# PoE.net
KiCad netlist of a schematic drawn in Altium Designer
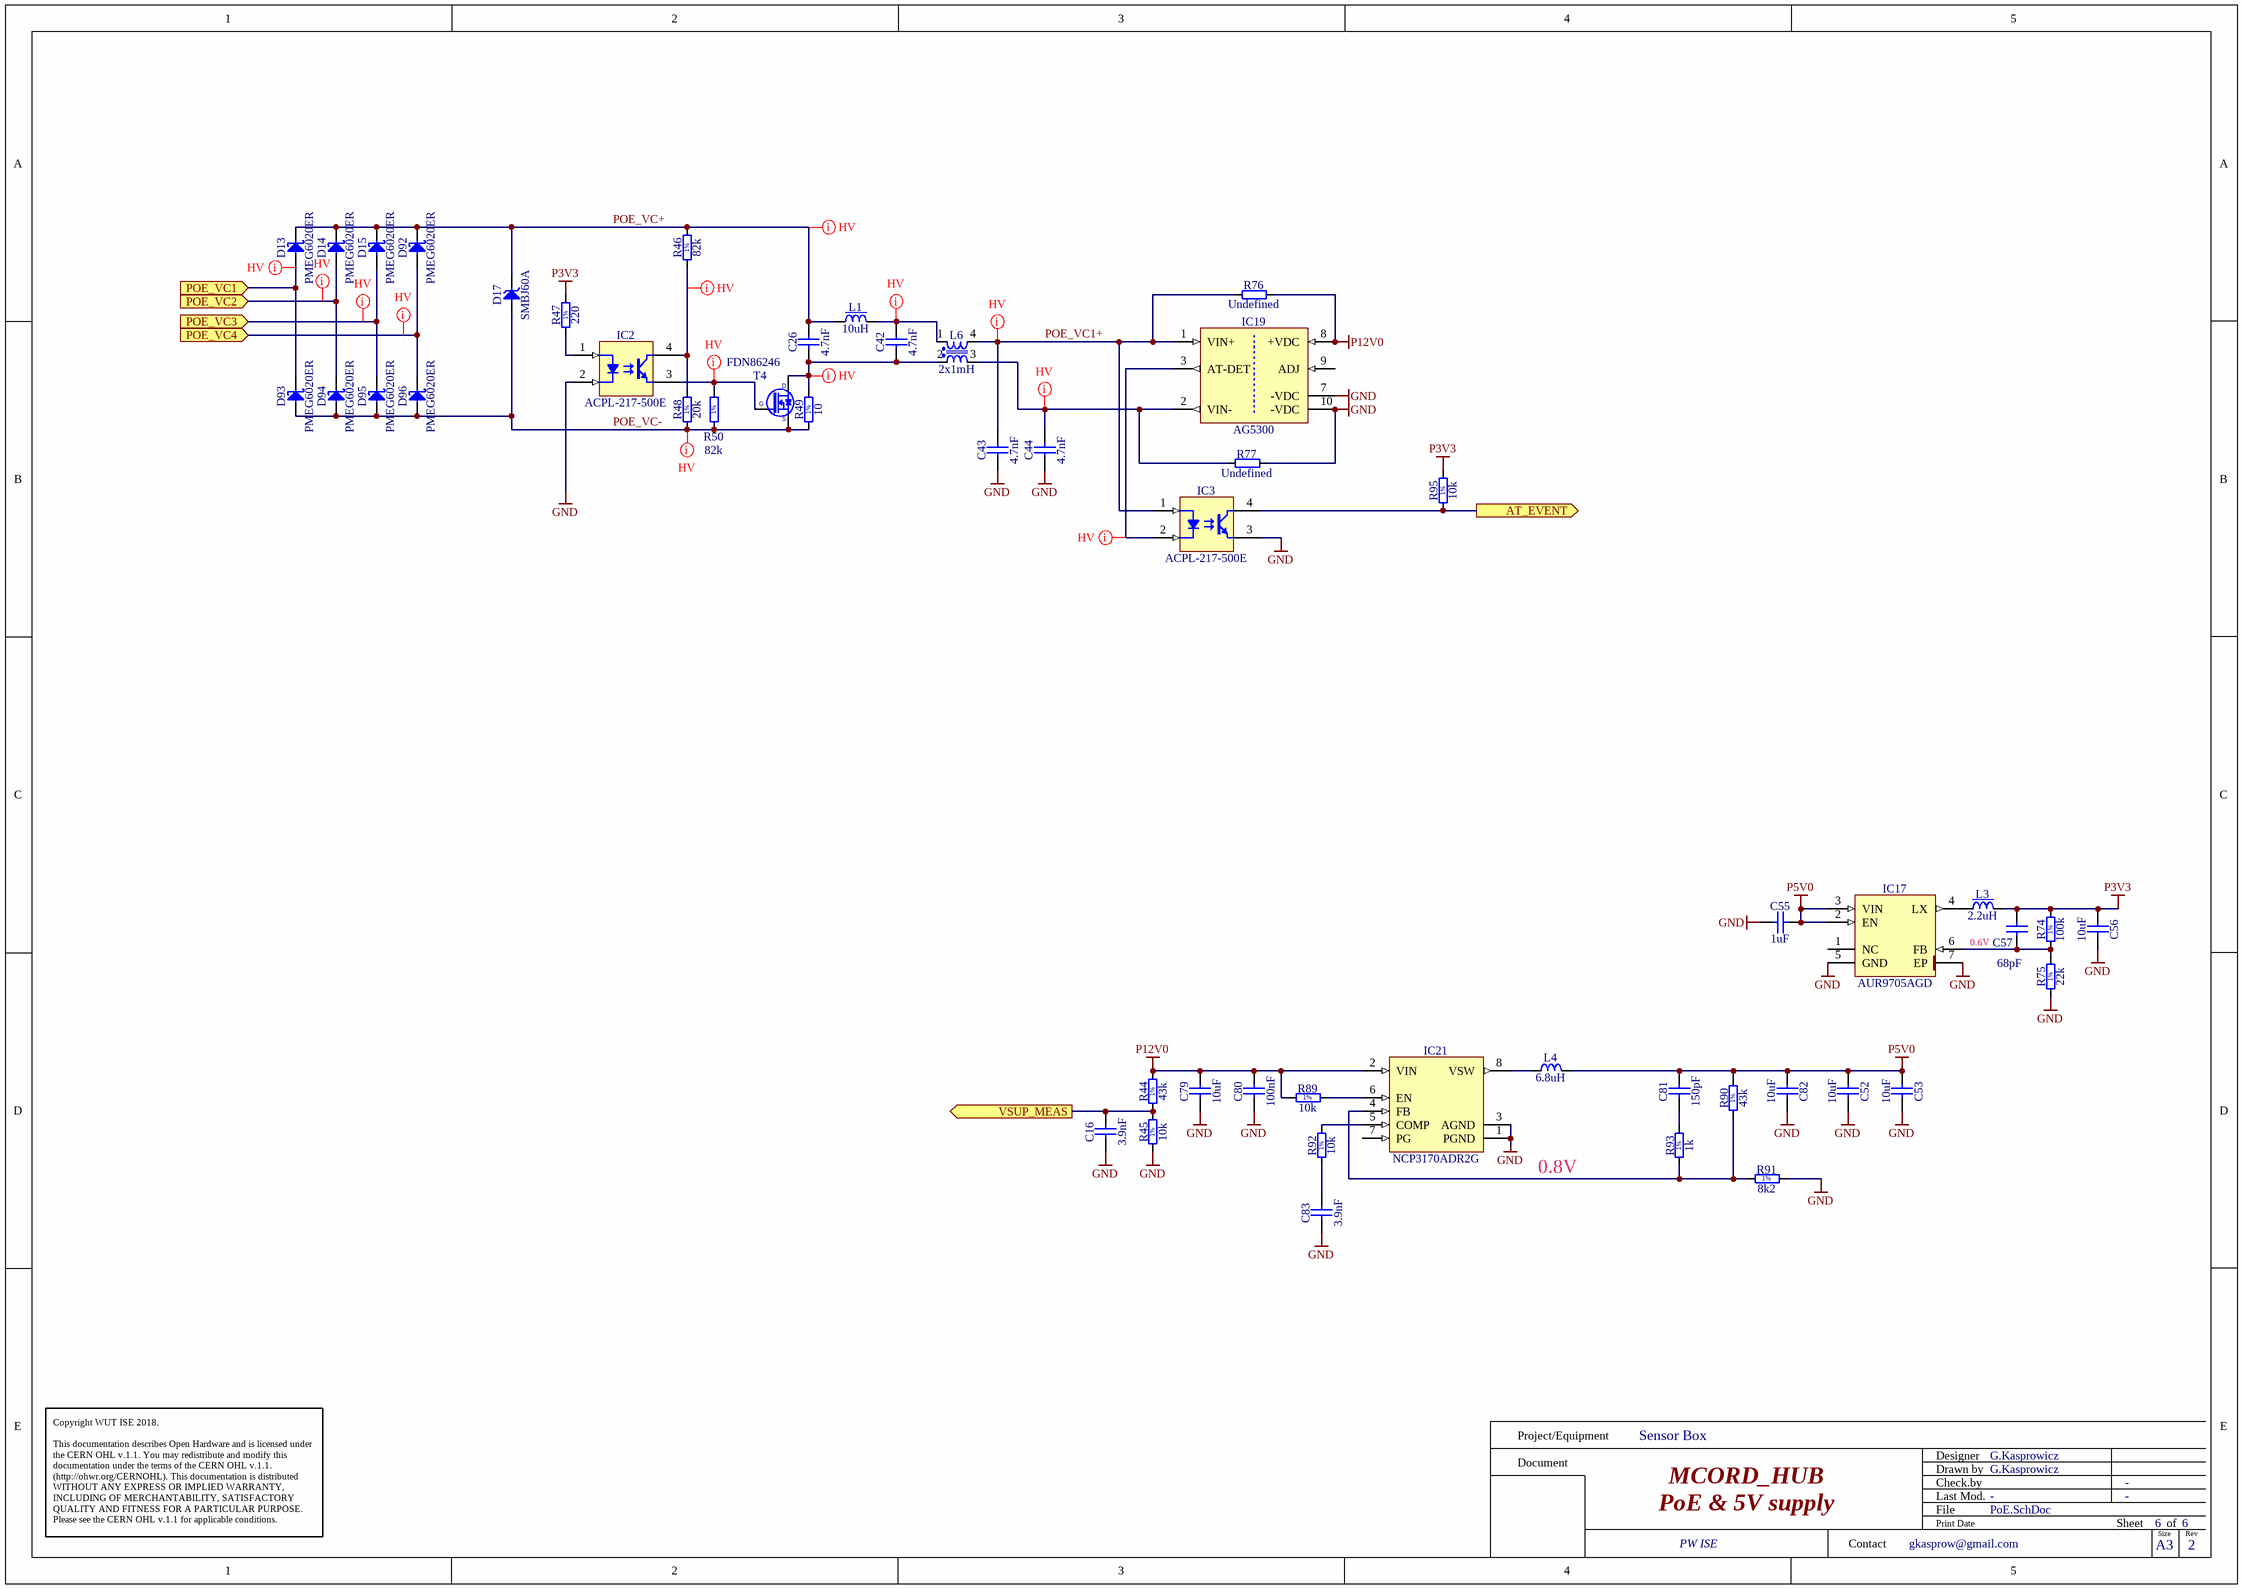
[diagram p0: PoE.SchDoc]

(export (version "E")
  (design (tool "Eeschema 10.0.6"))
  (components
    (comp (ref "C16")
      (value "3.9nF")
      (footprint "CAPC1608X87N")
      (description "Non-polarised capacitor")
      (fields
        (field (name "PART NUMBER") "CC0603_3.9NF_50V_5%_X7R")
        (field (name "VOLTAGE") "50V")
        (field (name "AUTHOR") "CERN DEM JLC")
      )
      (libsource (lib "Capacitors") (part "Capacitor - non polarized"))
    )
    (comp (ref "C26")
      (value "4.7nF")
      (footprint "CAPC3216X140N")
      (description "Non-polarised capacitor")
      (fields
        (field (name "PART NUMBER") "CC1206_4.7NF_500V_10%_X7R")
        (field (name "VOLTAGE") "500V")
        (field (name "AUTHOR") "GK")
      )
      (libsource (lib "LIBRARY_SCH") (part "CAP_SMD_1206_4.7n_500V"))
    )
    (comp (ref "C42")
      (value "4.7nF")
      (footprint "CAPC3216X140N")
      (description "Non-polarised capacitor")
      (fields
        (field (name "PART NUMBER") "CC1206_4.7NF_500V_10%_X7R")
        (field (name "VOLTAGE") "500V")
        (field (name "AUTHOR") "GK")
      )
      (libsource (lib "LIBRARY_SCH") (part "CAP_SMD_1206_4.7n_500V"))
    )
    (comp (ref "C43")
      (value "4.7nF")
      (footprint "CAPC3216X140N")
      (description "Non-polarised capacitor")
      (fields
        (field (name "PART NUMBER") "CC1206_4.7NF_500V_10%_X7R")
        (field (name "VOLTAGE") "500V")
        (field (name "AUTHOR") "GK")
      )
      (libsource (lib "LIBRARY_SCH") (part "CAP_SMD_1206_4.7n_500V"))
    )
    (comp (ref "C44")
      (value "4.7nF")
      (footprint "CAPC3216X140N")
      (description "Non-polarised capacitor")
      (fields
        (field (name "PART NUMBER") "CC1206_4.7NF_500V_10%_X7R")
        (field (name "VOLTAGE") "500V")
        (field (name "AUTHOR") "GK")
      )
      (libsource (lib "LIBRARY_SCH") (part "CAP_SMD_1206_4.7n_500V"))
    )
    (comp (ref "C52")
      (value "10uF")
      (footprint "CAPC2012X135N")
      (description "Non-polarised capacitor")
      (fields
        (field (name "PART NUMBER") "CC0805_10UF_16V_10%_X5R")
        (field (name "VOLTAGE") "16V")
        (field (name "AUTHOR") "CERN DEM JLC")
      )
      (libsource (lib "Capacitors") (part "Capacitor - non polarized"))
    )
    (comp (ref "C53")
      (value "10uF")
      (footprint "CAPC2012X135N")
      (description "Non-polarised capacitor")
      (fields
        (field (name "PART NUMBER") "CC0805_10UF_16V_10%_X5R")
        (field (name "VOLTAGE") "16V")
        (field (name "AUTHOR") "CERN DEM JLC")
      )
      (libsource (lib "Capacitors") (part "Capacitor - non polarized"))
    )
    (comp (ref "C55")
      (value "1uF")
      (footprint "CAPC1608X87N")
      (description "Non-polarised capacitor")
      (fields
        (field (name "PART NUMBER") "CC0603_1UF_16V_10%_X7R")
        (field (name "VOLTAGE") "16V")
        (field (name "AUTHOR") "CERN DEM JLC")
      )
      (libsource (lib "Capacitors") (part "Capacitor - non polarized"))
    )
    (comp (ref "C56")
      (value "10uF")
      (footprint "CAPC2012X135N")
      (description "Non-polarised capacitor")
      (fields
        (field (name "PART NUMBER") "CC0805_10UF_16V_10%_X5R")
        (field (name "VOLTAGE") "16V")
        (field (name "AUTHOR") "CERN DEM JLC")
      )
      (libsource (lib "Capacitors") (part "Capacitor - non polarized"))
    )
    (comp (ref "C57")
      (value "68pF")
      (footprint "CAPC1608X87N")
      (description "Non-polarised capacitor")
      (fields
        (field (name "PART NUMBER") "CC0603_68PF_50V_5%_NP0")
        (field (name "VOLTAGE") "50V")
        (field (name "AUTHOR") "CERN DEM JLC")
      )
      (libsource (lib "Capacitors") (part "Capacitor - non polarized"))
    )
    (comp (ref "C79")
      (value "10uF")
      (footprint "CAPC2012X135N")
      (description "Non-polarised capacitor")
      (fields
        (field (name "PART NUMBER") "CC0805_10UF_16V_10%_X5R")
        (field (name "VOLTAGE") "16V")
        (field (name "AUTHOR") "CERN DEM JLC")
      )
      (libsource (lib "Capacitors") (part "Capacitor - non polarized"))
    )
    (comp (ref "C80")
      (value "100nF")
      (footprint "CAPC1005X55N")
      (description "Non-polarised capacitor")
      (fields
        (field (name "PART NUMBER") "CC0402_100NF_16V_10%_X7R")
        (field (name "VOLTAGE") "16V")
        (field (name "AUTHOR") "CERN DEM JLC")
      )
      (libsource (lib "Capacitors") (part "Capacitor - non polarized"))
    )
    (comp (ref "C81")
      (value "150pF")
      (footprint "CAPC1608X87N")
      (description "Non-polarised capacitor")
      (fields
        (field (name "PART NUMBER") "CC0603_150PF_50V_1%_NP0")
        (field (name "VOLTAGE") "50V")
        (field (name "AUTHOR") "CERN DEM MR")
      )
      (libsource (lib "Capacitors") (part "Capacitor - non polarized"))
    )
    (comp (ref "C82")
      (value "10uF")
      (footprint "CAPC2012X135N")
      (description "Non-polarised capacitor")
      (fields
        (field (name "PART NUMBER") "CC0805_10UF_16V_10%_X5R")
        (field (name "VOLTAGE") "16V")
        (field (name "AUTHOR") "CERN DEM JLC")
      )
      (libsource (lib "Capacitors") (part "Capacitor - non polarized"))
    )
    (comp (ref "C83")
      (value "3.9nF")
      (footprint "CAPC1608X87N")
      (description "Non-polarised capacitor")
      (fields
        (field (name "PART NUMBER") "CC0603_3.9NF_50V_5%_X7R")
        (field (name "VOLTAGE") "50V")
        (field (name "AUTHOR") "CERN DEM JLC")
      )
      (libsource (lib "Capacitors") (part "Capacitor - non polarized"))
    )
    (comp (ref "D13")
      (value "PMEG6020ER")
      (footprint "SODFL3517X110N")
      (description "Schottky Diode")
      (fields
        (field (name "VOLTAGE") "60V")
        (field (name "POWER") "2A")
        (field (name "AUTHOR") "CERN DEM JMW")
      )
      (libsource (lib "ICs And Semiconductors") (part "Diode Schottky"))
    )
    (comp (ref "D14")
      (value "PMEG6020ER")
      (footprint "SODFL3517X110N")
      (description "Schottky Diode")
      (fields
        (field (name "VOLTAGE") "60V")
        (field (name "POWER") "2A")
        (field (name "AUTHOR") "CERN DEM JMW")
      )
      (libsource (lib "ICs And Semiconductors") (part "Diode Schottky"))
    )
    (comp (ref "D15")
      (value "PMEG6020ER")
      (footprint "SODFL3517X110N")
      (description "Schottky Diode")
      (fields
        (field (name "VOLTAGE") "60V")
        (field (name "POWER") "2A")
        (field (name "AUTHOR") "CERN DEM JMW")
      )
      (libsource (lib "ICs And Semiconductors") (part "Diode Schottky"))
    )
    (comp (ref "D17")
      (value "SMBJ60A")
      (footprint "DIOM5336X265N")
      (description "Zener Diode")
      (fields
        (field (name "VOLTAGE") "60V")
        (field (name "POWER") "600W")
        (field (name "AUTHOR") "CERN DEM JLC")
      )
      (libsource (lib "ICs And Semiconductors") (part "Diode Zener"))
    )
    (comp (ref "D92")
      (value "PMEG6020ER")
      (footprint "SODFL3517X110N")
      (description "Schottky Diode")
      (fields
        (field (name "VOLTAGE") "60V")
        (field (name "POWER") "2A")
        (field (name "AUTHOR") "CERN DEM JMW")
      )
      (libsource (lib "ICs And Semiconductors") (part "Diode Schottky"))
    )
    (comp (ref "D93")
      (value "PMEG6020ER")
      (footprint "SODFL3517X110N")
      (description "Schottky Diode")
      (fields
        (field (name "VOLTAGE") "60V")
        (field (name "POWER") "2A")
        (field (name "AUTHOR") "CERN DEM JMW")
      )
      (libsource (lib "ICs And Semiconductors") (part "Diode Schottky"))
    )
    (comp (ref "D94")
      (value "PMEG6020ER")
      (footprint "SODFL3517X110N")
      (description "Schottky Diode")
      (fields
        (field (name "VOLTAGE") "60V")
        (field (name "POWER") "2A")
        (field (name "AUTHOR") "CERN DEM JMW")
      )
      (libsource (lib "ICs And Semiconductors") (part "Diode Schottky"))
    )
    (comp (ref "D95")
      (value "PMEG6020ER")
      (footprint "SODFL3517X110N")
      (description "Schottky Diode")
      (fields
        (field (name "VOLTAGE") "60V")
        (field (name "POWER") "2A")
        (field (name "AUTHOR") "CERN DEM JMW")
      )
      (libsource (lib "ICs And Semiconductors") (part "Diode Schottky"))
    )
    (comp (ref "D96")
      (value "PMEG6020ER")
      (footprint "SODFL3517X110N")
      (description "Schottky Diode")
      (fields
        (field (name "VOLTAGE") "60V")
        (field (name "POWER") "2A")
        (field (name "AUTHOR") "CERN DEM JMW")
      )
      (libsource (lib "ICs And Semiconductors") (part "Diode Schottky"))
    )
    (comp (ref "IC2")
      (value "ACPL-217-500E")
      (footprint "SOIC127P700X242-4N")
      (description "Single Optocoupler")
      (fields (field (name "MANUFACTURER") "AVAGO TECHNOLOGIES") (field (name "AUTHOR") "CERN DEM JLC"))
      (libsource (lib "ICs And Semiconductors") (part "Optocoupler Type7"))
    )
    (comp (ref "IC3")
      (value "ACPL-217-500E")
      (footprint "SOIC127P700X242-4N")
      (description "Single Optocoupler")
      (fields (field (name "MANUFACTURER") "AVAGO TECHNOLOGIES") (field (name "AUTHOR") "CERN DEM JLC"))
      (libsource (lib "ICs And Semiconductors") (part "Optocoupler Type7"))
    )
    (comp (ref "IC17")
      (value "AUR9705AGD")
      (footprint "SON65P200X200X80-7N-R65X145")
      (description "0V to 6V Input, 1A, 1.5MHz, Step-Down DC-DC Converter")
      (fields (field (name "MANUFACTURER") "DIODES INCORPORATED") (field (name "AUTHOR") "CERN DEM MR"))
      (libsource (lib "ICs And Semiconductors") (part "AUR9705AGD"))
    )
    (comp (ref "IC19")
      (value "AG5300")
      (footprint "SILVERTEL_AG5300")
      (description "Power-over-Ethernet Plus (POE+) Module")
      (fields (field (name "MANUFACTURER") "SILVERTEL") (field (name "AUTHOR") "CERN DEM JLC"))
      (libsource (lib "ICs And Semiconductors") (part "AG5300"))
    )
    (comp (ref "IC21")
      (value "NCP3170ADR2G")
      (footprint "SOIC127P600X175-8N")
      (description "Synchronous PWM Switching Converter")
      (fields (field (name "MANUFACTURER") "ON SEMICONDUCTOR") (field (name "AUTHOR") "CERN DEM MR"))
      (libsource (lib "ICs And Semiconductors") (part "NCP3170ADR2G"))
    )
    (comp (ref "L1")
      (value "10uH")
      (footprint "IND_MURATA-PS_8400")
      (description "Inductor With Core")
      (fields
        (field (name "PART NUMBER") "IND_10UH_10%_MURATA-PS_8400")
        (field (name "POWER") "950mA")
        (field (name "AUTHOR") "CERN DEM JLC")
      )
      (libsource (lib "Inductors & Transformers") (part "Inductor With Magnetic core"))
    )
    (comp (ref "L3")
      (value "2.2uH")
      (footprint "IND_MURATA_LQH44PN_P0")
      (description "Inductor With Core")
      (fields
        (field (name "PART NUMBER") "IND_2.2UH_20%_MURATA_LQH44PN2R2MP0L")
        (field (name "POWER") "1.8A")
        (field (name "AUTHOR") "CERN DEM JLC")
      )
      (libsource (lib "Inductors & Transformers") (part "Inductor With Magnetic core"))
    )
    (comp (ref "L4")
      (value "6.8uH")
      (footprint "IND_BOURNS_SRU8043")
      (description "Inductor")
      (fields
        (field (name "PART NUMBER") "IND_6.8UH_30%_BOURNS_SRU8043")
        (field (name "POWER") "3.8A")
        (field (name "AUTHOR") "CERN DEM JMW")
      )
      (libsource (lib "Inductors & Transformers") (part "Inductor"))
    )
    (comp (ref "L6")
      (value "2x1mH")
      (footprint "IND_WURTH_WE-SL2")
      (description "Inductor Common Mode")
      (fields
        (field (name "PART NUMBER") "IND_1MH_50%_WURTH_WE-SL2-744222")
        (field (name "POWER") "800mA")
        (field (name "AUTHOR") "CERN DEM JLC")
      )
      (libsource (lib "Inductors & Transformers") (part "Inductor Common Mode 1Dot-4 2Dot-3"))
    )
    (comp (ref "R44")
      (value "43k")
      (footprint "RESC1608X55N")
      (description "Resistor - 1%")
      (fields
        (field (name "PART NUMBER") "R0603_43K_1%_0.1W_100PPM")
        (field (name "POWER") "0.1W")
        (field (name "AUTHOR") "CERN DEM JLC")
      )
      (libsource (lib "Resistors") (part "Resistor - 1%"))
    )
    (comp (ref "R45")
      (value "10k")
      (footprint "RESC1005X40N")
      (description "Resistor - 1%")
      (fields
        (field (name "PART NUMBER") "R0402_10K_1%_0.0625W_100PPM")
        (field (name "POWER") "0.0625W")
        (field (name "AUTHOR") "CERN DEM JLC")
      )
      (libsource (lib "Resistors") (part "Resistor - 1%"))
    )
    (comp (ref "R46")
      (value "82k")
      (footprint "RESC1608X55N")
      (description "Resistor - 1%")
      (fields
        (field (name "PART NUMBER") "R0603_82K_1%_0.1W_100PPM")
        (field (name "POWER") "0.1W")
        (field (name "AUTHOR") "CERN DEM JLC")
      )
      (libsource (lib "Resistors") (part "Resistor - 1%"))
    )
    (comp (ref "R47")
      (value "220")
      (footprint "RESC1608X55N")
      (description "Resistor - 1%")
      (fields
        (field (name "PART NUMBER") "R0603_220R_1%_0.1W_100PPM")
        (field (name "POWER") "0.1W")
        (field (name "AUTHOR") "CERN DEM JLC")
      )
      (libsource (lib "Resistors") (part "Resistor - 1%"))
    )
    (comp (ref "R48")
      (value "20k")
      (footprint "RESC1005X40N")
      (description "Resistor - 1%")
      (fields
        (field (name "PART NUMBER") "R0402_20K_1%_0.0625W_100PPM")
        (field (name "POWER") "0.0625W")
        (field (name "AUTHOR") "CERN DEM JLC")
      )
      (libsource (lib "Resistors") (part "Resistor - 1%"))
    )
    (comp (ref "R49")
      (value "10")
      (footprint "RESC2012X60N")
      (description "Resistor - 1%")
      (fields
        (field (name "PART NUMBER") "R0805_10R_1%_0.125W_200PPM")
        (field (name "POWER") "0.125W")
        (field (name "AUTHOR") "CERN DEM JLC")
      )
      (libsource (lib "Resistors") (part "Resistor - 1%"))
    )
    (comp (ref "R50")
      (value "82k")
      (footprint "RESC1608X55N")
      (description "Resistor - 1%")
      (fields
        (field (name "PART NUMBER") "R0603_82K_1%_0.1W_100PPM")
        (field (name "POWER") "0.1W")
        (field (name "AUTHOR") "CERN DEM JLC")
      )
      (libsource (lib "Resistors") (part "Resistor - 1%"))
    )
    (comp (ref "R74")
      (value "100k")
      (footprint "RESC1005X40N")
      (description "Resistor - 1%")
      (fields
        (field (name "PART NUMBER") "R0402_100K_1%_0.0625W_100PPM")
        (field (name "POWER") "0.0625W")
        (field (name "AUTHOR") "CERN DEM JLC")
      )
      (libsource (lib "Resistors") (part "Resistor - 1%"))
    )
    (comp (ref "R75")
      (value "22k")
      (footprint "RESC1005X40N")
      (description "Resistor - 1%")
      (fields
        (field (name "PART NUMBER") "R0402_22K_1%_0.0625W_100PPM")
        (field (name "POWER") "0.0625W")
        (field (name "AUTHOR") "CERN DEM JLC")
      )
      (libsource (lib "Resistors") (part "Resistor - 1%"))
    )
    (comp (ref "R76")
      (value "Undefined")
      (footprint "RESC3216X65N")
      (description "Resistor")
      (fields (field (name "PART NUMBER") "R1206_NO-VALUE") (field (name "AUTHOR") "CERN DEM JLC"))
      (libsource (lib "Resistors") (part "Resistor"))
    )
    (comp (ref "R77")
      (value "Undefined")
      (footprint "RESC3216X65N")
      (description "Resistor")
      (fields (field (name "PART NUMBER") "R1206_NO-VALUE") (field (name "AUTHOR") "CERN DEM JLC"))
      (libsource (lib "Resistors") (part "Resistor"))
    )
    (comp (ref "R89")
      (value "10k")
      (footprint "RESC1005X40N")
      (description "Resistor - 1%")
      (fields
        (field (name "PART NUMBER") "R0402_10K_1%_0.0625W_100PPM")
        (field (name "POWER") "0.0625W")
        (field (name "AUTHOR") "CERN DEM JLC")
      )
      (libsource (lib "Resistors") (part "Resistor - 1%"))
    )
    (comp (ref "R90")
      (value "43k")
      (footprint "RESC1608X55N")
      (description "Resistor - 1%")
      (fields
        (field (name "PART NUMBER") "R0603_43K_1%_0.1W_100PPM")
        (field (name "POWER") "0.1W")
        (field (name "AUTHOR") "CERN DEM JLC")
      )
      (libsource (lib "Resistors") (part "Resistor - 1%"))
    )
    (comp (ref "R91")
      (value "8k2")
      (footprint "RESC1608X55N")
      (description "Resistor - 1%")
      (fields
        (field (name "PART NUMBER") "R0603_8K2_1%_0.1W_100PPM")
        (field (name "POWER") "0.1W")
        (field (name "AUTHOR") "CERN DEM JLC")
      )
      (libsource (lib "Resistors") (part "Resistor - 1%"))
    )
    (comp (ref "R92")
      (value "10k")
      (footprint "RESC1005X40N")
      (description "Resistor - 1%")
      (fields
        (field (name "PART NUMBER") "R0402_10K_1%_0.0625W_100PPM")
        (field (name "POWER") "0.0625W")
        (field (name "AUTHOR") "CERN DEM JLC")
      )
      (libsource (lib "Resistors") (part "Resistor - 1%"))
    )
    (comp (ref "R93")
      (value "1k")
      (footprint "RESC1005X40N")
      (description "Resistor - 1%")
      (fields
        (field (name "PART NUMBER") "R0402_1K_1%_0.0625W_100PPM")
        (field (name "POWER") "0.0625W")
        (field (name "AUTHOR") "CERN DEM JLC")
      )
      (libsource (lib "Resistors") (part "Resistor - 1%"))
    )
    (comp (ref "R95")
      (value "10k")
      (footprint "RESC1005X40N")
      (description "Resistor - 1%")
      (fields
        (field (name "PART NUMBER") "R0402_10K_1%_0.0625W_100PPM")
        (field (name "POWER") "0.0625W")
        (field (name "AUTHOR") "CERN DEM JLC")
      )
      (libsource (lib "Resistors") (part "Resistor - 1%"))
    )
    (comp (ref "T4")
      (value "FDN86246")
      (footprint "SOT95P237X112-3N")
      (description "N-CHANNEL MOSFET WITH DIODE")
      (fields (field (name "MANUFACTURER") "ON SEMICONDUCTOR") (field (name "AUTHOR") "CERN DEM BC"))
      (libsource (lib "ICs And Semiconductors") (part "N-MOSFET-D 1G 2S 3D"))
    )
  )
  (nets
    (net (code "1") (name "/AT_EVENT") (class "Default")
      (node (ref "IC3") (pin "4") (pinfunction "C_4") (pintype "open_collector"))
      (node (ref "R95") (pin "1") (pinfunction "1_1") (pintype "passive"))
    )
    (net (code "2") (name "/POE_VC+") (class "Default")
      (node (ref "C26") (pin "2") (pinfunction "2_2") (pintype "passive"))
      (node (ref "D13") (pin "1") (pinfunction "C_1") (pintype "passive"))
      (node (ref "D14") (pin "1") (pinfunction "C_1") (pintype "passive"))
      (node (ref "D15") (pin "1") (pinfunction "C_1") (pintype "passive"))
      (node (ref "D17") (pin "1") (pinfunction "C_1") (pintype "passive"))
      (node (ref "D92") (pin "1") (pinfunction "C_1") (pintype "passive"))
      (node (ref "L1") (pin "1") (pinfunction "1_1") (pintype "passive"))
      (node (ref "R46") (pin "2") (pinfunction "2_2") (pintype "passive"))
    )
    (net (code "3") (name "/POE_VC-") (class "Default")
      (node (ref "D17") (pin "2") (pinfunction "A_2") (pintype "passive"))
      (node (ref "D93") (pin "2") (pinfunction "A_2") (pintype "passive"))
      (node (ref "D94") (pin "2") (pinfunction "A_2") (pintype "passive"))
      (node (ref "D95") (pin "2") (pinfunction "A_2") (pintype "passive"))
      (node (ref "D96") (pin "2") (pinfunction "A_2") (pintype "passive"))
      (node (ref "R48") (pin "1") (pinfunction "1_1") (pintype "passive"))
      (node (ref "R49") (pin "1") (pinfunction "1_1") (pintype "passive"))
      (node (ref "R50") (pin "1") (pinfunction "1_1") (pintype "passive"))
      (node (ref "T4") (pin "2") (pinfunction "S_2") (pintype "passive"))
    )
    (net (code "4") (name "/POE_VC1") (class "Default")
      (node (ref "D13") (pin "2") (pinfunction "A_2") (pintype "passive"))
      (node (ref "D93") (pin "1") (pinfunction "C_1") (pintype "passive"))
    )
    (net (code "5") (name "/POE_VC1+") (class "Default")
      (node (ref "C43") (pin "2") (pinfunction "2_2") (pintype "passive"))
      (node (ref "IC19") (pin "1") (pinfunction "VIN+_1") (pintype "input"))
      (node (ref "IC3") (pin "1") (pinfunction "A_1") (pintype "input"))
      (node (ref "L6") (pin "4") (pinfunction "4_4") (pintype "passive"))
      (node (ref "R76") (pin "1") (pinfunction "1_1") (pintype "passive"))
    )
    (net (code "6") (name "/POE_VC2") (class "Default")
      (node (ref "D14") (pin "2") (pinfunction "A_2") (pintype "passive"))
      (node (ref "D94") (pin "1") (pinfunction "C_1") (pintype "passive"))
    )
    (net (code "7") (name "/POE_VC3") (class "Default")
      (node (ref "D15") (pin "2") (pinfunction "A_2") (pintype "passive"))
      (node (ref "D95") (pin "1") (pinfunction "C_1") (pintype "passive"))
    )
    (net (code "8") (name "/POE_VC4") (class "Default")
      (node (ref "D92") (pin "2") (pinfunction "A_2") (pintype "passive"))
      (node (ref "D96") (pin "1") (pinfunction "C_1") (pintype "passive"))
    )
    (net (code "9") (name "/VSUP_MEAS") (class "Default")
      (node (ref "C16") (pin "2") (pinfunction "2_2") (pintype "passive"))
      (node (ref "R44") (pin "1") (pinfunction "1_1") (pintype "passive"))
      (node (ref "R45") (pin "2") (pinfunction "2_2") (pintype "passive"))
    )
    (net (code "10") (name "GND") (class "Default")
      (node (ref "C16") (pin "1") (pinfunction "1_1") (pintype "passive"))
      (node (ref "C43") (pin "1") (pinfunction "1_1") (pintype "passive"))
      (node (ref "C44") (pin "1") (pinfunction "1_1") (pintype "passive"))
      (node (ref "C52") (pin "2") (pinfunction "2_2") (pintype "passive"))
      (node (ref "C53") (pin "2") (pinfunction "2_2") (pintype "passive"))
      (node (ref "C55") (pin "1") (pinfunction "1_1") (pintype "passive"))
      (node (ref "C56") (pin "2") (pinfunction "2_2") (pintype "passive"))
      (node (ref "C79") (pin "1") (pinfunction "1_1") (pintype "passive"))
      (node (ref "C80") (pin "1") (pinfunction "1_1") (pintype "passive"))
      (node (ref "C82") (pin "2") (pinfunction "2_2") (pintype "passive"))
      (node (ref "C83") (pin "1") (pinfunction "1_1") (pintype "passive"))
      (node (ref "IC17") (pin "5") (pinfunction "GND_5") (pintype "power_in"))
      (node (ref "IC17") (pin "7") (pinfunction "EP_7") (pintype "passive"))
      (node (ref "IC19") (pin "10") (pinfunction "-VDC_10") (pintype "power_in"))
      (node (ref "IC19") (pin "7") (pinfunction "-VDC_7") (pintype "power_in"))
      (node (ref "IC2") (pin "2") (pinfunction "C_2") (pintype "input"))
      (node (ref "IC21") (pin "1") (pinfunction "PGND_1") (pintype "power_in"))
      (node (ref "IC21") (pin "3") (pinfunction "AGND_3") (pintype "power_in"))
      (node (ref "IC3") (pin "3") (pinfunction "E_3") (pintype "open_emitter"))
      (node (ref "R45") (pin "1") (pinfunction "1_1") (pintype "passive"))
      (node (ref "R75") (pin "1") (pinfunction "1_1") (pintype "passive"))
      (node (ref "R77") (pin "2") (pinfunction "2_2") (pintype "passive"))
      (node (ref "R91") (pin "2") (pinfunction "2_2") (pintype "passive"))
    )
    (net (code "11") (name "Net-(C42-Pad2)") (class "Default")
      (node (ref "C42") (pin "2") (pinfunction "2_2") (pintype "passive"))
      (node (ref "L1") (pin "2") (pinfunction "2_2") (pintype "passive"))
      (node (ref "L6") (pin "1") (pinfunction "1_1") (pintype "passive"))
    )
    (net (code "12") (name "Net-(C81-Pad1)") (class "Default")
      (node (ref "C81") (pin "1") (pinfunction "1_1") (pintype "passive"))
      (node (ref "R93") (pin "2") (pinfunction "2_2") (pintype "passive"))
    )
    (net (code "13") (name "Net-(C83-Pad2)") (class "Default")
      (node (ref "C83") (pin "2") (pinfunction "2_2") (pintype "passive"))
      (node (ref "R92") (pin "1") (pinfunction "1_1") (pintype "passive"))
    )
    (net (code "14") (name "Net-(IC2-A)") (class "Default")
      (node (ref "IC2") (pin "1") (pinfunction "A_1") (pintype "input"))
      (node (ref "R47") (pin "1") (pinfunction "1_1") (pintype "passive"))
    )
    (net (code "15") (name "Net-(IC2-C-Pad4)") (class "Default")
      (node (ref "IC2") (pin "4") (pinfunction "C_4") (pintype "open_collector"))
      (node (ref "R46") (pin "1") (pinfunction "1_1") (pintype "passive"))
      (node (ref "R48") (pin "2") (pinfunction "2_2") (pintype "passive"))
    )
    (net (code "16") (name "Net-(IC2-E)") (class "Default")
      (node (ref "IC2") (pin "3") (pinfunction "E_3") (pintype "open_emitter"))
      (node (ref "R50") (pin "2") (pinfunction "2_2") (pintype "passive"))
      (node (ref "T4") (pin "1") (pinfunction "G_1") (pintype "passive"))
    )
    (net (code "17") (name "Net-(IC17-FB)") (class "Default")
      (node (ref "C57") (pin "1") (pinfunction "1_1") (pintype "passive"))
      (node (ref "IC17") (pin "6") (pinfunction "FB_6") (pintype "input"))
      (node (ref "R74") (pin "1") (pinfunction "1_1") (pintype "passive"))
      (node (ref "R75") (pin "2") (pinfunction "2_2") (pintype "passive"))
    )
    (net (code "18") (name "Net-(IC17-LX)") (class "Default")
      (node (ref "IC17") (pin "4") (pinfunction "LX_4") (pintype "output"))
      (node (ref "L3") (pin "1") (pinfunction "1_1") (pintype "passive"))
    )
    (net (code "19") (name "Net-(IC19-AT-DET)") (class "Default")
      (node (ref "IC19") (pin "3") (pinfunction "AT-DET_3") (pintype "output"))
      (node (ref "IC3") (pin "2") (pinfunction "C_2") (pintype "input"))
    )
    (net (code "20") (name "Net-(IC19-VIN-)") (class "Default")
      (node (ref "C44") (pin "2") (pinfunction "2_2") (pintype "passive"))
      (node (ref "IC19") (pin "2") (pinfunction "VIN-_2") (pintype "output"))
      (node (ref "L6") (pin "3") (pinfunction "3_3") (pintype "passive"))
      (node (ref "R77") (pin "1") (pinfunction "1_1") (pintype "passive"))
    )
    (net (code "21") (name "Net-(IC21-COMP)") (class "Default")
      (node (ref "IC21") (pin "5") (pinfunction "COMP_5") (pintype "input"))
      (node (ref "R92") (pin "2") (pinfunction "2_2") (pintype "passive"))
    )
    (net (code "22") (name "Net-(IC21-EN)") (class "Default")
      (node (ref "IC21") (pin "6") (pinfunction "EN_6") (pintype "input"))
      (node (ref "R89") (pin "2") (pinfunction "2_2") (pintype "passive"))
    )
    (net (code "23") (name "Net-(IC21-FB)") (class "Default")
      (node (ref "IC21") (pin "4") (pinfunction "FB_4") (pintype "input"))
      (node (ref "R90") (pin "1") (pinfunction "1_1") (pintype "passive"))
      (node (ref "R91") (pin "1") (pinfunction "1_1") (pintype "passive"))
      (node (ref "R93") (pin "1") (pinfunction "1_1") (pintype "passive"))
    )
    (net (code "24") (name "Net-(IC21-VSW)") (class "Default")
      (node (ref "IC21") (pin "8") (pinfunction "VSW_8") (pintype "output"))
      (node (ref "L4") (pin "1") (pinfunction "1_1") (pintype "passive"))
    )
    (net (code "25") (name "Net-(T4-D)") (class "Default")
      (node (ref "C26") (pin "1") (pinfunction "1_1") (pintype "passive"))
      (node (ref "C42") (pin "1") (pinfunction "1_1") (pintype "passive"))
      (node (ref "L6") (pin "2") (pinfunction "2_2") (pintype "passive"))
      (node (ref "R49") (pin "2") (pinfunction "2_2") (pintype "passive"))
      (node (ref "T4") (pin "3") (pinfunction "D_3") (pintype "passive"))
    )
    (net (code "26") (name "P3V3") (class "Default")
      (node (ref "C56") (pin "1") (pinfunction "1_1") (pintype "passive"))
      (node (ref "C57") (pin "2") (pinfunction "2_2") (pintype "passive"))
      (node (ref "L3") (pin "2") (pinfunction "2_2") (pintype "passive"))
      (node (ref "R47") (pin "2") (pinfunction "2_2") (pintype "passive"))
      (node (ref "R74") (pin "2") (pinfunction "2_2") (pintype "passive"))
      (node (ref "R95") (pin "2") (pinfunction "2_2") (pintype "passive"))
    )
    (net (code "27") (name "P5V0") (class "Default")
      (node (ref "C52") (pin "1") (pinfunction "1_1") (pintype "passive"))
      (node (ref "C53") (pin "1") (pinfunction "1_1") (pintype "passive"))
      (node (ref "C55") (pin "2") (pinfunction "2_2") (pintype "passive"))
      (node (ref "C81") (pin "2") (pinfunction "2_2") (pintype "passive"))
      (node (ref "C82") (pin "1") (pinfunction "1_1") (pintype "passive"))
      (node (ref "IC17") (pin "2") (pinfunction "EN_2") (pintype "input"))
      (node (ref "IC17") (pin "3") (pinfunction "VIN_3") (pintype "input"))
      (node (ref "L4") (pin "2") (pinfunction "2_2") (pintype "passive"))
      (node (ref "R90") (pin "2") (pinfunction "2_2") (pintype "passive"))
    )
    (net (code "28") (name "P12V0") (class "Default")
      (node (ref "C79") (pin "2") (pinfunction "2_2") (pintype "passive"))
      (node (ref "C80") (pin "2") (pinfunction "2_2") (pintype "passive"))
      (node (ref "IC19") (pin "8") (pinfunction "+VDC_8") (pintype "input"))
      (node (ref "IC21") (pin "2") (pinfunction "VIN_2") (pintype "input"))
      (node (ref "R44") (pin "2") (pinfunction "2_2") (pintype "passive"))
      (node (ref "R76") (pin "2") (pinfunction "2_2") (pintype "passive"))
      (node (ref "R89") (pin "1") (pinfunction "1_1") (pintype "passive"))
    )
    (net (code "29") (name "unconnected-(IC17-NC-Pad1)") (class "Default")
      (node (ref "IC17") (pin "1") (pinfunction "NC_1") (pintype "passive"))
    )
    (net (code "30") (name "unconnected-(IC19-ADJ-Pad9)") (class "Default")
      (node (ref "IC19") (pin "9") (pinfunction "ADJ_9") (pintype "input"))
    )
    (net (code "31") (name "unconnected-(IC21-PG-Pad7)") (class "Default")
      (node (ref "IC21") (pin "7") (pinfunction "PG_7") (pintype "input"))
    )
  )
)
